# 06_AUDIO.net
KiCad netlist of a schematic drawn in Altium Designer
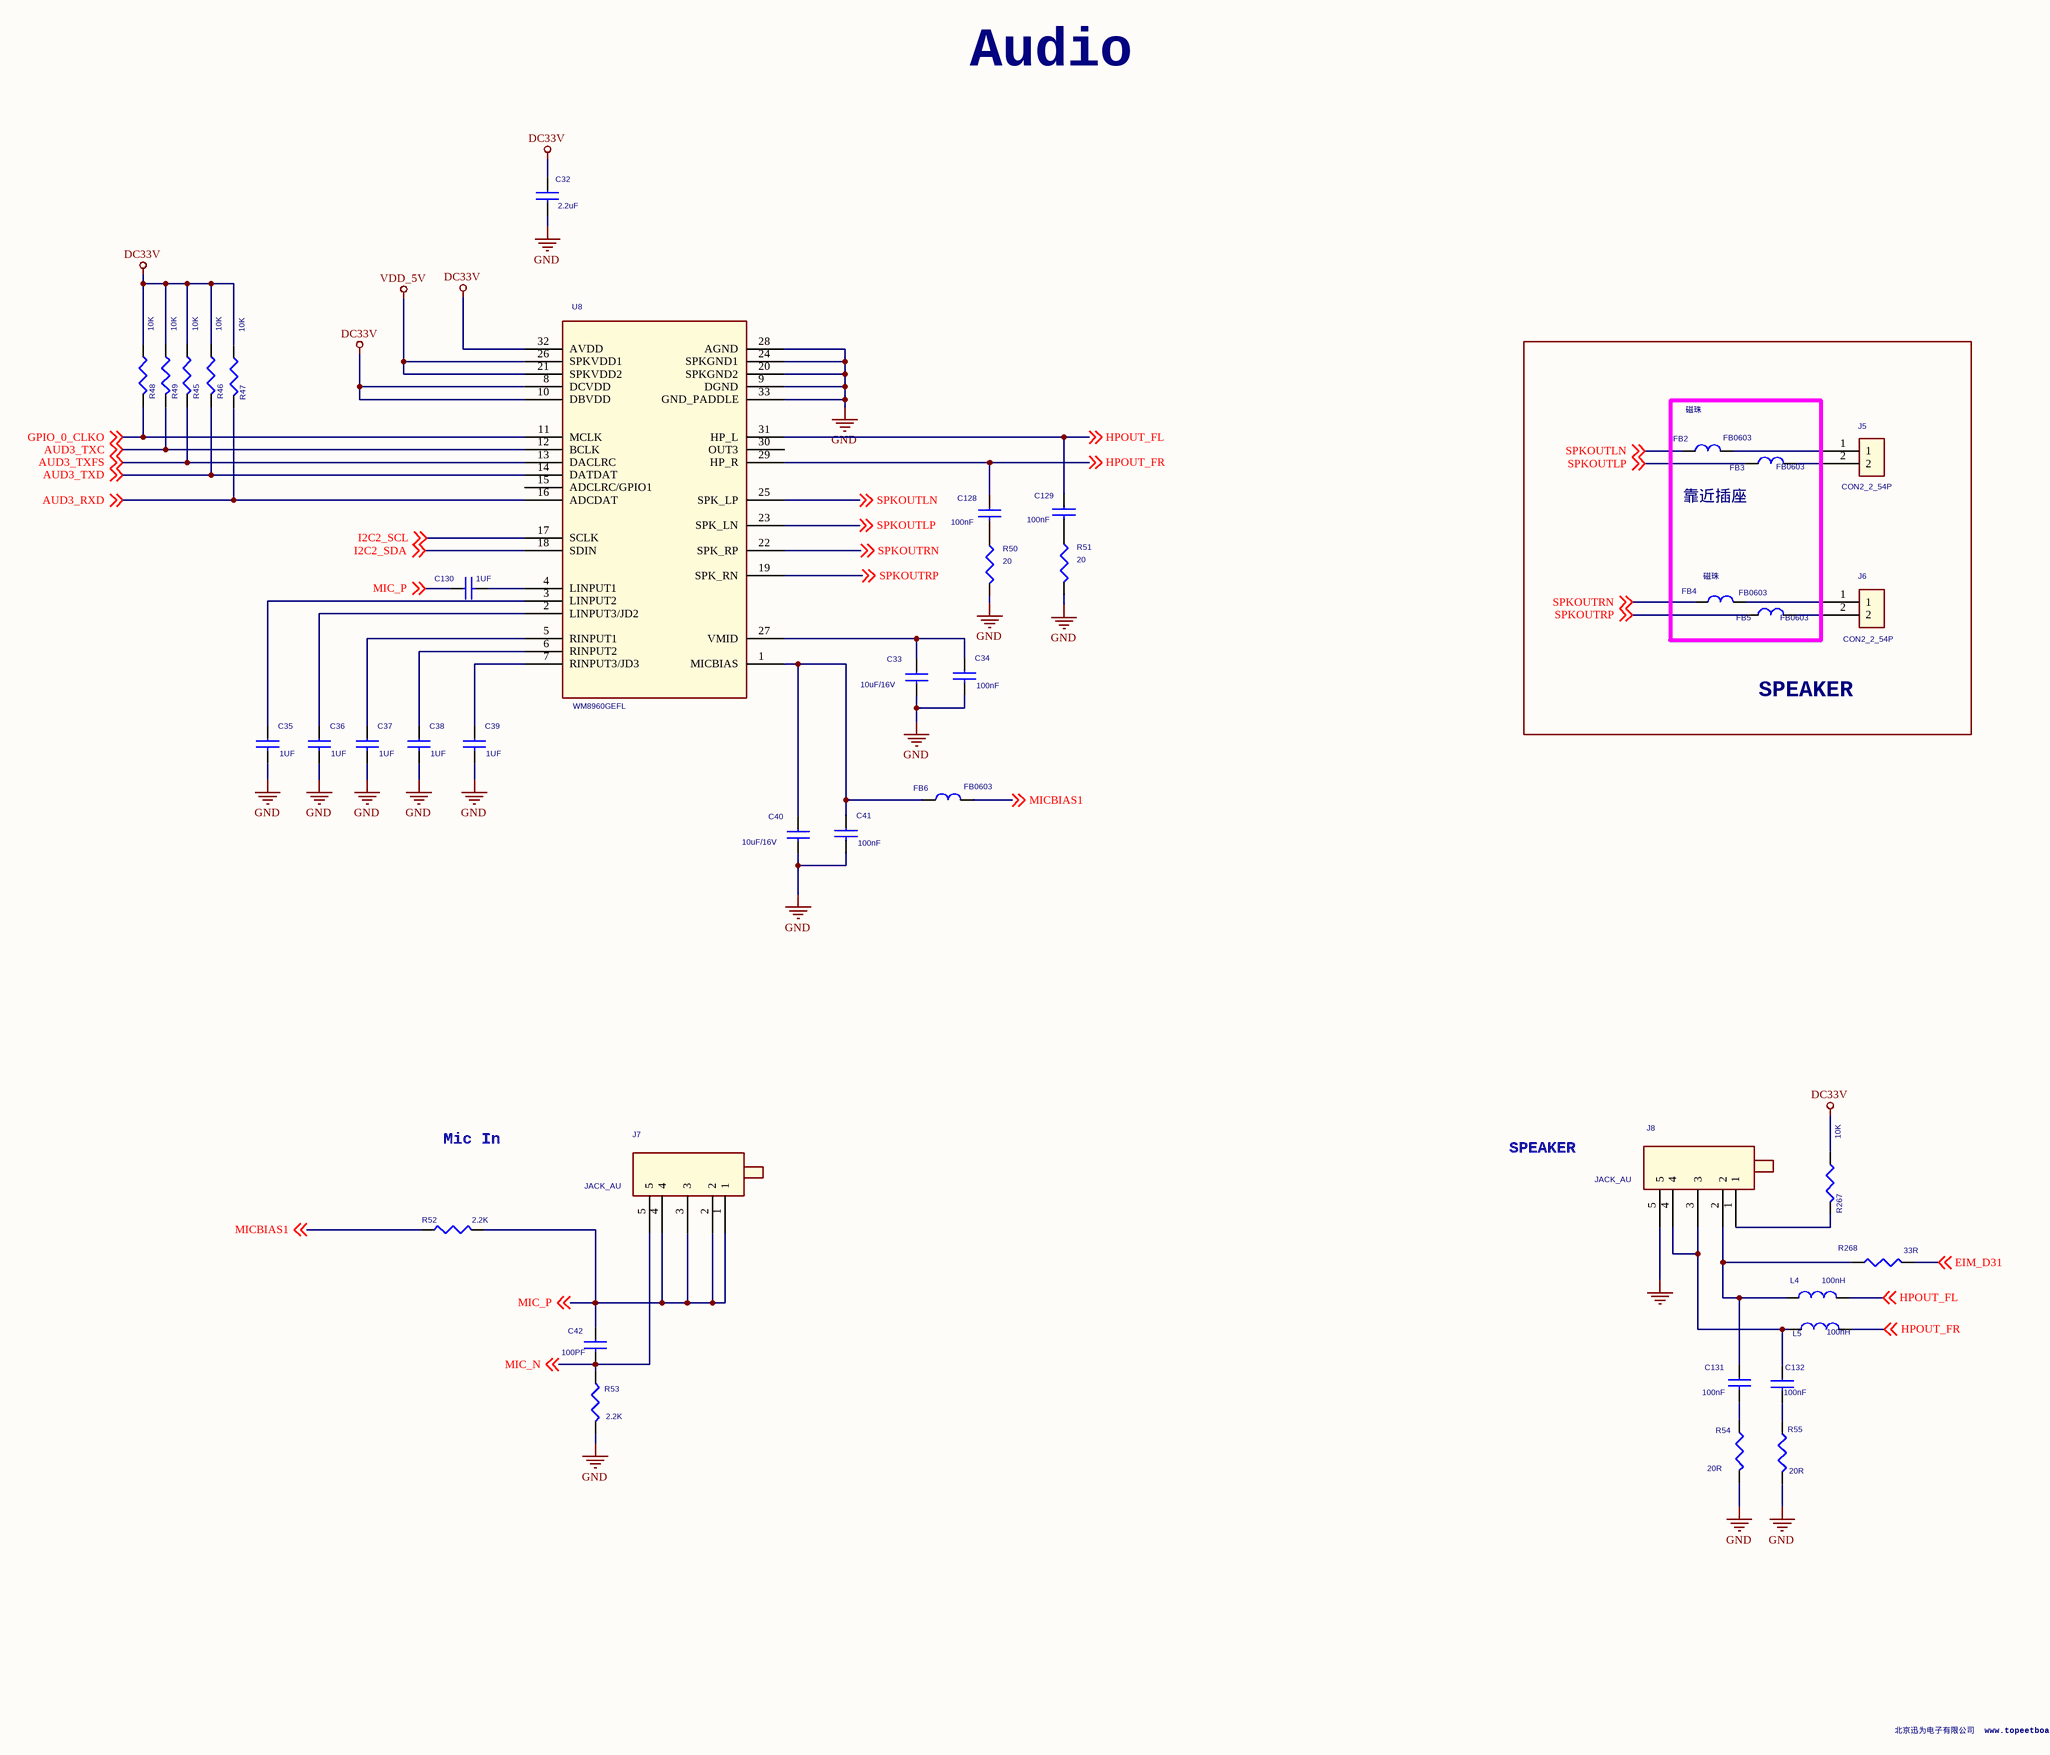
[diagram p0: 06 AUDIO.SchDoc]

(export (version "E")
  (design (tool "Eeschema 10.0.6"))
  (components
    (comp (ref "C32") (value "2.2uF") (footprint "C0603") (libsource (lib "*") (part "C0603_0_Dup1")))
    (comp (ref "C33") (value "10uF/16V") (footprint "C0603") (libsource (lib "*") (part "C0603_0_Dup1")))
    (comp (ref "C34") (value "100nF") (footprint "C0603") (libsource (lib "*") (part "C0603_0_Dup1")))
    (comp (ref "C35") (value "1UF") (footprint "C0603") (libsource (lib "*") (part "C0603_0_Dup1")))
    (comp (ref "C36") (value "1UF") (footprint "C0603") (libsource (lib "*") (part "C0603_0_Dup1")))
    (comp (ref "C37") (value "1UF") (footprint "C0603") (libsource (lib "*") (part "C0603_0_Dup1")))
    (comp (ref "C38") (value "1UF") (footprint "C0603") (libsource (lib "*") (part "C0603_0_Dup1")))
    (comp (ref "C39") (value "1UF") (footprint "C0603") (libsource (lib "*") (part "C0603_0_Dup1")))
    (comp (ref "C40") (value "10uF/16V") (footprint "C0603") (libsource (lib "*") (part "C0603_0_Dup1")))
    (comp (ref "C41") (value "100nF") (footprint "C0603") (libsource (lib "*") (part "C0603_0_Dup1")))
    (comp (ref "C42") (value "100PF") (footprint "C1608") (libsource (lib "*") (part "C1608")))
    (comp (ref "C128") (value "100nF") (footprint "C1608") (libsource (lib "*") (part "C1608_Dup1")))
    (comp (ref "C129") (value "100nF") (footprint "C1608") (libsource (lib "*") (part "C1608_Dup1")))
    (comp (ref "C130") (value "1UF") (footprint "C1608") (libsource (lib "*") (part "C1608_Dup1")))
    (comp (ref "C131") (value "100nF") (footprint "C1608") (libsource (lib "*") (part "C1608_Dup1")))
    (comp (ref "C132") (value "100nF") (footprint "C1608") (libsource (lib "*") (part "C1608_Dup1")))
    (comp (ref "FB2") (value "FB0603") (footprint "1206-A") (libsource (lib "*") (part "FB1206_0")))
    (comp (ref "FB3") (value "FB0603") (footprint "1206-A") (libsource (lib "*") (part "FB1206_0")))
    (comp (ref "FB4") (value "FB0603") (footprint "1206-A") (libsource (lib "*") (part "FB1206_0")))
    (comp (ref "FB5") (value "FB0603") (footprint "1206-A") (libsource (lib "*") (part "FB1206_0")))
    (comp (ref "FB6") (value "FB0603") (footprint "1206-A") (libsource (lib "*") (part "FB1206_0")))
    (comp (ref "J5") (value "CON2_2_54P") (libsource (lib "*") (part "CON2_2_54P")))
    (comp (ref "J6") (value "CON2_2_54P") (libsource (lib "*") (part "CON2_2_54P")))
    (comp (ref "J7") (value "JACK_AU") (libsource (lib "*") (part "JACK_AU")))
    (comp (ref "J8") (value "JACK_AU") (libsource (lib "*") (part "JACK_AU")))
    (comp (ref "L4") (value "100nH") (footprint "LQH32C") (libsource (lib "*") (part "LQH32C_0_Dup2")))
    (comp (ref "L5") (value "100nH") (footprint "LQH32C") (libsource (lib "*") (part "LQH32C_0_Dup2")))
    (comp (ref "R45") (value "10K") (libsource (lib "*") (part "R")))
    (comp (ref "R46") (value "10K") (libsource (lib "*") (part "R")))
    (comp (ref "R47") (value "10K") (libsource (lib "*") (part "R")))
    (comp (ref "R48") (value "10K") (libsource (lib "*") (part "R")))
    (comp (ref "R49") (value "10K") (libsource (lib "*") (part "R")))
    (comp (ref "R50") (value "20") (footprint "R1005") (libsource (lib "*") (part "R1005_0_Dup1")))
    (comp (ref "R51") (value "20") (footprint "R1005") (libsource (lib "*") (part "R1005_0_Dup1")))
    (comp (ref "R52") (value "2.2K") (footprint "R1005") (libsource (lib "*") (part "R1005_0_Dup1")))
    (comp (ref "R53") (value "2.2K") (footprint "R1005") (libsource (lib "*") (part "R1005_0_Dup1")))
    (comp (ref "R54") (value "20R") (footprint "R1005") (libsource (lib "*") (part "R1005_0_Dup1")))
    (comp (ref "R55") (value "20R") (footprint "R1005") (libsource (lib "*") (part "R1005_0_Dup1")))
    (comp (ref "R267") (value "10K") (libsource (lib "*") (part "R")))
    (comp (ref "R268") (value "33R") (footprint "R1005") (libsource (lib "*") (part "R1005_0_Dup1")))
    (comp (ref "U8") (value "WM8960GEFL") (libsource (lib "*") (part "WM8960GEFL_0")))
  )
  (nets
    (net (code "1") (name "AUD3_RXD") (class "Default")
      (node (ref "R47") (pin "2") (pinfunction "2_2") (pintype "passive"))
      (node (ref "U8") (pin "16") (pinfunction "ADCDAT_16") (pintype "passive"))
    )
    (net (code "2") (name "AUD3_TXC") (class "Default")
      (node (ref "R49") (pin "2") (pinfunction "2_2") (pintype "passive"))
      (node (ref "U8") (pin "12") (pinfunction "BCLK_12") (pintype "passive"))
    )
    (net (code "3") (name "AUD3_TXD") (class "Default")
      (node (ref "R46") (pin "2") (pinfunction "2_2") (pintype "passive"))
      (node (ref "U8") (pin "14") (pinfunction "DATDAT_14") (pintype "passive"))
    )
    (net (code "4") (name "AUD3_TXFS") (class "Default")
      (node (ref "R45") (pin "2") (pinfunction "2_2") (pintype "passive"))
      (node (ref "U8") (pin "13") (pinfunction "DACLRC_13") (pintype "passive"))
    )
    (net (code "5") (name "DC33V") (class "Default")
      (node (ref "C32") (pin "1") (pinfunction "1_1") (pintype "passive"))
      (node (ref "R267") (pin "1") (pinfunction "1_1") (pintype "passive"))
      (node (ref "R45") (pin "1") (pinfunction "1_1") (pintype "passive"))
      (node (ref "R46") (pin "1") (pinfunction "1_1") (pintype "passive"))
      (node (ref "R47") (pin "1") (pinfunction "1_1") (pintype "passive"))
      (node (ref "R48") (pin "1") (pinfunction "1_1") (pintype "passive"))
      (node (ref "R49") (pin "1") (pinfunction "1_1") (pintype "passive"))
      (node (ref "U8") (pin "10") (pinfunction "DBVDD_10") (pintype "passive"))
      (node (ref "U8") (pin "32") (pinfunction "AVDD_32") (pintype "passive"))
      (node (ref "U8") (pin "8") (pinfunction "DCVDD_8") (pintype "passive"))
    )
    (net (code "6") (name "EIM_D31") (class "Default")
      (node (ref "R268") (pin "2") (pinfunction "2_2") (pintype "passive"))
    )
    (net (code "7") (name "GND") (class "Default")
      (node (ref "C32") (pin "2") (pinfunction "2_2") (pintype "passive"))
      (node (ref "C33") (pin "2") (pinfunction "2_2") (pintype "passive"))
      (node (ref "C34") (pin "2") (pinfunction "2_2") (pintype "passive"))
      (node (ref "C35") (pin "2") (pinfunction "2_2") (pintype "passive"))
      (node (ref "C36") (pin "2") (pinfunction "2_2") (pintype "passive"))
      (node (ref "C37") (pin "2") (pinfunction "2_2") (pintype "passive"))
      (node (ref "C38") (pin "2") (pinfunction "2_2") (pintype "passive"))
      (node (ref "C39") (pin "2") (pinfunction "2_2") (pintype "passive"))
      (node (ref "C40") (pin "2") (pinfunction "2_2") (pintype "passive"))
      (node (ref "C41") (pin "2") (pinfunction "2_2") (pintype "passive"))
      (node (ref "J8") (pin "5") (pinfunction "5_5") (pintype "passive"))
      (node (ref "R50") (pin "2") (pinfunction "2_2") (pintype "passive"))
      (node (ref "R51") (pin "2") (pinfunction "2_2") (pintype "passive"))
      (node (ref "R53") (pin "2") (pinfunction "2_2") (pintype "passive"))
      (node (ref "R54") (pin "2") (pinfunction "2_2") (pintype "passive"))
      (node (ref "R55") (pin "2") (pinfunction "2_2") (pintype "passive"))
      (node (ref "U8") (pin "20") (pinfunction "SPKGND2_20") (pintype "passive"))
      (node (ref "U8") (pin "24") (pinfunction "SPKGND1_24") (pintype "passive"))
      (node (ref "U8") (pin "28") (pinfunction "AGND_28") (pintype "passive"))
      (node (ref "U8") (pin "33") (pinfunction "GND_PADDLE_33") (pintype "passive"))
      (node (ref "U8") (pin "9") (pinfunction "DGND_9") (pintype "passive"))
    )
    (net (code "8") (name "GPIO_0_CLKO") (class "Default")
      (node (ref "R48") (pin "2") (pinfunction "2_2") (pintype "passive"))
      (node (ref "U8") (pin "11") (pinfunction "MCLK_11") (pintype "passive"))
    )
    (net (code "9") (name "HPOUT_FL") (class "Default")
      (node (ref "C129") (pin "1") (pinfunction "1_1") (pintype "passive"))
      (node (ref "L4") (pin "2") (pinfunction "2_2") (pintype "passive"))
      (node (ref "U8") (pin "31") (pinfunction "HP_L_31") (pintype "passive"))
    )
    (net (code "10") (name "HPOUT_FR") (class "Default")
      (node (ref "C128") (pin "1") (pinfunction "1_1") (pintype "passive"))
      (node (ref "L5") (pin "2") (pinfunction "2_2") (pintype "passive"))
      (node (ref "U8") (pin "29") (pinfunction "HP_R_29") (pintype "passive"))
    )
    (net (code "11") (name "I2C2_SCL") (class "Default")
      (node (ref "U8") (pin "17") (pinfunction "SCLK_17") (pintype "passive"))
    )
    (net (code "12") (name "I2C2_SDA") (class "Default")
      (node (ref "U8") (pin "18") (pinfunction "SDIN_18") (pintype "passive"))
    )
    (net (code "13") (name "MICBIAS1") (class "Default")
      (node (ref "FB6") (pin "2") (pinfunction "2_2") (pintype "passive"))
      (node (ref "R52") (pin "1") (pinfunction "1_1") (pintype "passive"))
    )
    (net (code "14") (name "MIC_N") (class "Default")
      (node (ref "C42") (pin "2") (pinfunction "2_2") (pintype "passive"))
      (node (ref "J7") (pin "5") (pinfunction "5_5") (pintype "passive"))
      (node (ref "R53") (pin "1") (pinfunction "1_1") (pintype "passive"))
    )
    (net (code "15") (name "MIC_P") (class "Default")
      (node (ref "C130") (pin "1") (pinfunction "1_1") (pintype "passive"))
      (node (ref "C42") (pin "1") (pinfunction "1_1") (pintype "passive"))
      (node (ref "J7") (pin "1") (pinfunction "1_1") (pintype "passive"))
      (node (ref "J7") (pin "2") (pinfunction "2_2") (pintype "passive"))
      (node (ref "J7") (pin "3") (pinfunction "3_3") (pintype "passive"))
      (node (ref "J7") (pin "4") (pinfunction "4_4") (pintype "passive"))
      (node (ref "R52") (pin "2") (pinfunction "2_2") (pintype "passive"))
    )
    (net (code "16") (name "Net-(C128-Pad2)") (class "Default")
      (node (ref "C128") (pin "2") (pinfunction "2_2") (pintype "passive"))
      (node (ref "R50") (pin "1") (pinfunction "1_1") (pintype "passive"))
    )
    (net (code "17") (name "Net-(C129-Pad2)") (class "Default")
      (node (ref "C129") (pin "2") (pinfunction "2_2") (pintype "passive"))
      (node (ref "R51") (pin "1") (pinfunction "1_1") (pintype "passive"))
    )
    (net (code "18") (name "Net-(C131-Pad1)") (class "Default")
      (node (ref "C131") (pin "1") (pinfunction "1_1") (pintype "passive"))
      (node (ref "J8") (pin "2") (pinfunction "2_2") (pintype "passive"))
      (node (ref "L4") (pin "1") (pinfunction "1_1") (pintype "passive"))
      (node (ref "R268") (pin "1") (pinfunction "1_1") (pintype "passive"))
    )
    (net (code "19") (name "Net-(C131-Pad2)") (class "Default")
      (node (ref "C131") (pin "2") (pinfunction "2_2") (pintype "passive"))
      (node (ref "R54") (pin "1") (pinfunction "1_1") (pintype "passive"))
    )
    (net (code "20") (name "Net-(C132-Pad1)") (class "Default")
      (node (ref "C132") (pin "1") (pinfunction "1_1") (pintype "passive"))
      (node (ref "J8") (pin "3") (pinfunction "3_3") (pintype "passive"))
      (node (ref "J8") (pin "4") (pinfunction "4_4") (pintype "passive"))
      (node (ref "L5") (pin "1") (pinfunction "1_1") (pintype "passive"))
    )
    (net (code "21") (name "Net-(C132-Pad2)") (class "Default")
      (node (ref "C132") (pin "2") (pinfunction "2_2") (pintype "passive"))
      (node (ref "R55") (pin "1") (pinfunction "1_1") (pintype "passive"))
    )
    (net (code "22") (name "Net-(FB2-Pad2)") (class "Default")
      (node (ref "FB2") (pin "2") (pinfunction "2_2") (pintype "passive"))
      (node (ref "J5") (pin "1") (pinfunction "1_1") (pintype "passive"))
    )
    (net (code "23") (name "Net-(FB3-Pad2)") (class "Default")
      (node (ref "FB3") (pin "2") (pinfunction "2_2") (pintype "passive"))
      (node (ref "J5") (pin "2") (pinfunction "2_2") (pintype "passive"))
    )
    (net (code "24") (name "Net-(FB4-Pad2)") (class "Default")
      (node (ref "FB4") (pin "2") (pinfunction "2_2") (pintype "passive"))
      (node (ref "J6") (pin "1") (pinfunction "1_1") (pintype "passive"))
    )
    (net (code "25") (name "Net-(FB5-Pad2)") (class "Default")
      (node (ref "FB5") (pin "2") (pinfunction "2_2") (pintype "passive"))
      (node (ref "J6") (pin "2") (pinfunction "2_2") (pintype "passive"))
    )
    (net (code "26") (name "Net-(J8-Pad1)") (class "Default")
      (node (ref "J8") (pin "1") (pinfunction "1_1") (pintype "passive"))
      (node (ref "R267") (pin "2") (pinfunction "2_2") (pintype "passive"))
    )
    (net (code "27") (name "Net-(U8-LINPUT1)") (class "Default")
      (node (ref "C130") (pin "2") (pinfunction "2_2") (pintype "passive"))
      (node (ref "U8") (pin "4") (pinfunction "LINPUT1_4") (pintype "passive"))
    )
    (net (code "28") (name "Net-(U8-LINPUT2)") (class "Default")
      (node (ref "C35") (pin "1") (pinfunction "1_1") (pintype "passive"))
      (node (ref "U8") (pin "3") (pinfunction "LINPUT2_3") (pintype "passive"))
    )
    (net (code "29") (name "Net-(U8-LINPUT3{slash}JD2)") (class "Default")
      (node (ref "C36") (pin "1") (pinfunction "1_1") (pintype "passive"))
      (node (ref "U8") (pin "2") (pinfunction "LINPUT3/JD2_2") (pintype "passive"))
    )
    (net (code "30") (name "Net-(U8-MICBIAS)") (class "Default")
      (node (ref "C40") (pin "1") (pinfunction "1_1") (pintype "passive"))
      (node (ref "C41") (pin "1") (pinfunction "1_1") (pintype "passive"))
      (node (ref "FB6") (pin "1") (pinfunction "1_1") (pintype "passive"))
      (node (ref "U8") (pin "1") (pinfunction "MICBIAS_1") (pintype "passive"))
    )
    (net (code "31") (name "Net-(U8-RINPUT1)") (class "Default")
      (node (ref "C37") (pin "1") (pinfunction "1_1") (pintype "passive"))
      (node (ref "U8") (pin "5") (pinfunction "RINPUT1_5") (pintype "passive"))
    )
    (net (code "32") (name "Net-(U8-RINPUT2)") (class "Default")
      (node (ref "C38") (pin "1") (pinfunction "1_1") (pintype "passive"))
      (node (ref "U8") (pin "6") (pinfunction "RINPUT2_6") (pintype "passive"))
    )
    (net (code "33") (name "Net-(U8-RINPUT3{slash}JD3)") (class "Default")
      (node (ref "C39") (pin "1") (pinfunction "1_1") (pintype "passive"))
      (node (ref "U8") (pin "7") (pinfunction "RINPUT3/JD3_7") (pintype "passive"))
    )
    (net (code "34") (name "Net-(U8-VMID)") (class "Default")
      (node (ref "C33") (pin "1") (pinfunction "1_1") (pintype "passive"))
      (node (ref "C34") (pin "1") (pinfunction "1_1") (pintype "passive"))
      (node (ref "U8") (pin "27") (pinfunction "VMID_27") (pintype "passive"))
    )
    (net (code "35") (name "SPKOUTLN") (class "Default")
      (node (ref "FB2") (pin "1") (pinfunction "1_1") (pintype "passive"))
      (node (ref "U8") (pin "25") (pinfunction "SPK_LP_25") (pintype "passive"))
    )
    (net (code "36") (name "SPKOUTLP") (class "Default")
      (node (ref "FB3") (pin "1") (pinfunction "1_1") (pintype "passive"))
      (node (ref "U8") (pin "23") (pinfunction "SPK_LN_23") (pintype "passive"))
    )
    (net (code "37") (name "SPKOUTRN") (class "Default")
      (node (ref "FB4") (pin "1") (pinfunction "1_1") (pintype "passive"))
      (node (ref "U8") (pin "22") (pinfunction "SPK_RP_22") (pintype "passive"))
    )
    (net (code "38") (name "SPKOUTRP") (class "Default")
      (node (ref "FB5") (pin "1") (pinfunction "1_1") (pintype "passive"))
      (node (ref "U8") (pin "19") (pinfunction "SPK_RN_19") (pintype "passive"))
    )
    (net (code "39") (name "VDD_5V") (class "Default")
      (node (ref "U8") (pin "21") (pinfunction "SPKVDD2_21") (pintype "passive"))
      (node (ref "U8") (pin "26") (pinfunction "SPKVDD1_26") (pintype "passive"))
    )
    (net (code "40") (name "unconnected-(U8-ADCLRC{slash}GPIO1-Pad15)") (class "Default")
      (node (ref "U8") (pin "15") (pinfunction "ADCLRC/GPIO1_15") (pintype "passive"))
    )
    (net (code "41") (name "unconnected-(U8-OUT3-Pad30)") (class "Default")
      (node (ref "U8") (pin "30") (pinfunction "OUT3_30") (pintype "passive"))
    )
  )
)
